# ESP32-Proto3-B.net
KiCad netlist of a schematic drawn in EAGLE
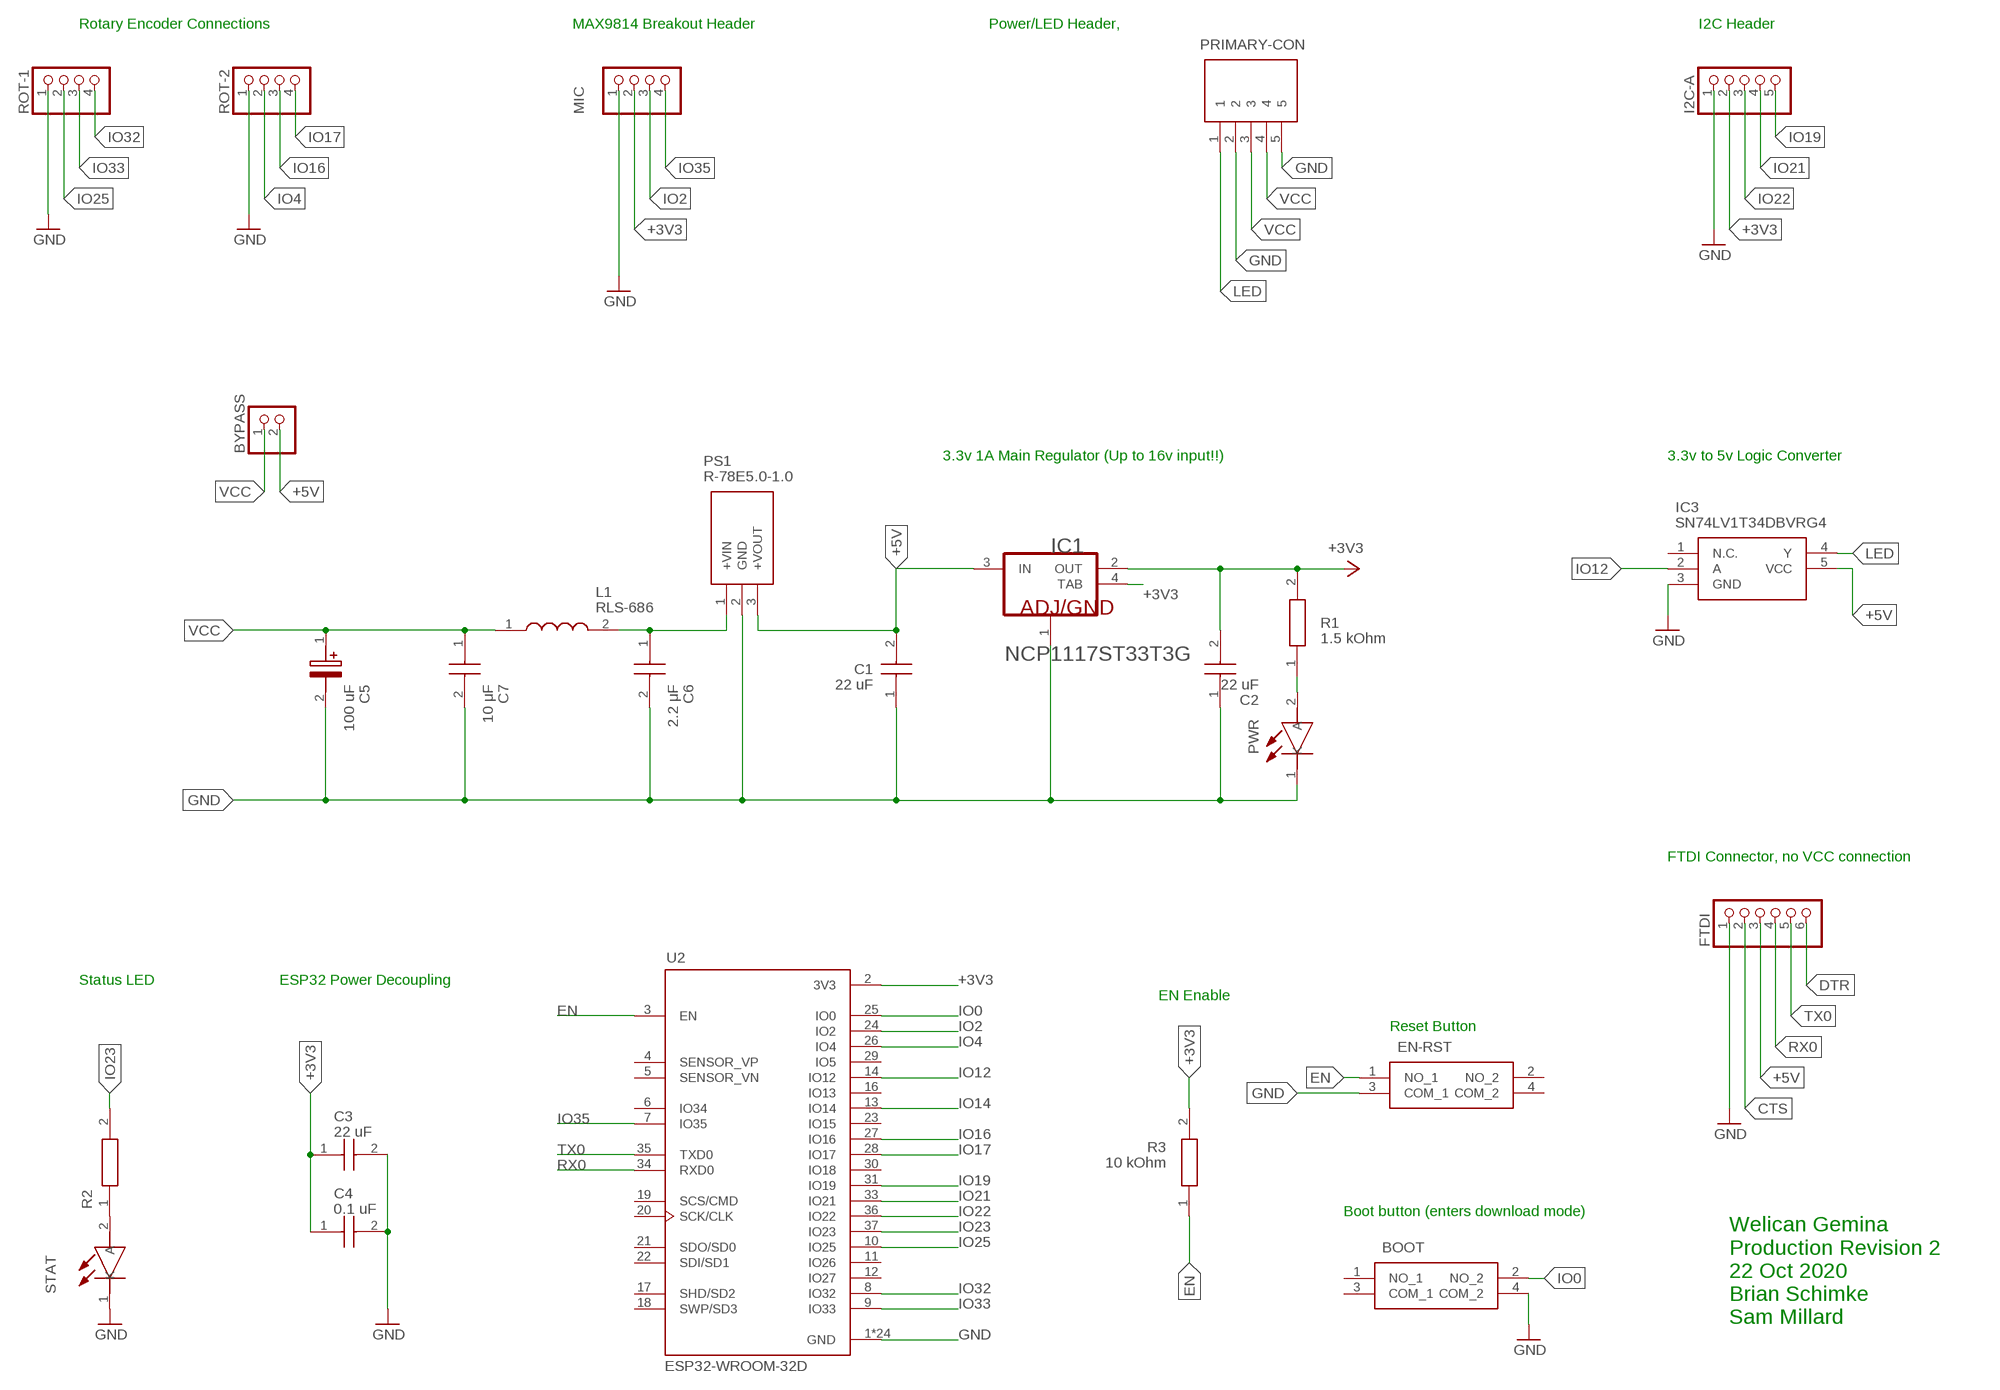
[diagram p0: schematic, sheet 1]

(export (version "E")
  (design (tool "Eeschema 10.0.6"))
  (components
    (comp (ref "BOOT")
      (value "PTS647SK70SMTR2LFS")
      (footprint "eagle-import:PTS647SK70SMTR2LFS")
      (fields (field (name "MOUSER_PART_NUMBER") "611-PTS647SK70SMTR2L"))
      (libsource (lib "eagle-import") (part "PTS647SK70SMTR2LFS"))
    )
    (comp (ref "BYPASS")
      (value "PINHD-1X2")
      (footprint "eagle-import:1X02")
      (libsource (lib "eagle-import") (part "PINHD-1X2"))
    )
    (comp (ref "C1")
      (value "22 uF")
      (footprint "eagle-import:CAPC3216X180N")
      (fields
        (field (name "MANUFACTURER_PART_NUMBER") "C1206C226M4PACTU")
        (field (name "MOUSER_PART_NUMBER") "80-C1206C226M4P")
      )
      (libsource (lib "eagle-import") (part "C1206C226M4PACTU"))
    )
    (comp (ref "C2")
      (value "22 uF")
      (footprint "eagle-import:CAPC3216X180N")
      (fields
        (field (name "MANUFACTURER_PART_NUMBER") "C1206C226M4PACTU")
        (field (name "MOUSER_PART_NUMBER") "80-C1206C226M4P")
      )
      (libsource (lib "eagle-import") (part "C1206C226M4PACTU"))
    )
    (comp (ref "C3")
      (value "22 uF")
      (footprint "eagle-import:CAPC3216X180N")
      (fields
        (field (name "MANUFACTURER_PART_NUMBER") "C1206C226M4PACTU")
        (field (name "MOUSER_PART_NUMBER") "80-C1206C226M4P")
      )
      (libsource (lib "eagle-import") (part "C1206C226M4PACTU"))
    )
    (comp (ref "C4")
      (value "0.1 uF")
      (footprint "eagle-import:CAPC3216X180N")
      (fields
        (field (name "MANUFACTURER_PART_NUMBER") "C1206C226M4PACTU")
        (field (name "MOUSER_PART_NUMBER") "80-C1206C226M4P")
      )
      (libsource (lib "eagle-import") (part "C1206C226M4PACTU"))
    )
    (comp (ref "C5")
      (value "100 uF")
      (footprint "eagle-import:CAPAE660X770N")
      (fields
        (field (name "MANUFACTURER_PART_NUMBER") "865080445010")
        (field (name "MOUSER_PART_NUMBER") "710-865080445010")
      )
      (libsource (lib "eagle-import") (part "865080445010"))
    )
    (comp (ref "C6")
      (value "2.2 μF")
      (footprint "eagle-import:CAPC3216X180N")
      (fields
        (field (name "MANUFACTURER_PART_NUMBER") "C1206C226M4PACTU")
        (field (name "MOUSER_PART_NUMBER") "80-C1206C226M4P")
      )
      (libsource (lib "eagle-import") (part "C1206C226M4PACTU"))
    )
    (comp (ref "C7")
      (value "10 μF")
      (footprint "eagle-import:CAPC3216X180N")
      (fields
        (field (name "MANUFACTURER_PART_NUMBER") "C1206C226M4PACTU")
        (field (name "MOUSER_PART_NUMBER") "80-C1206C226M4P")
      )
      (libsource (lib "eagle-import") (part "C1206C226M4PACTU"))
    )
    (comp (ref "EN-RST")
      (value "PTS647SK70SMTR2LFS")
      (footprint "eagle-import:PTS647SK70SMTR2LFS")
      (fields (field (name "MOUSER_PART_NUMBER") "611-PTS647SK70SMTR2L"))
      (libsource (lib "eagle-import") (part "PTS647SK70SMTR2LFS"))
    )
    (comp (ref "FTDI")
      (value "PINHD-1X6")
      (footprint "eagle-import:1X06")
      (libsource (lib "eagle-import") (part "PINHD-1X6"))
    )
    (comp (ref "I2C-A")
      (value "PINHD-1X5")
      (footprint "eagle-import:1X05")
      (libsource (lib "eagle-import") (part "PINHD-1X5"))
    )
    (comp (ref "IC1")
      (value "ON_SEMICONDUCTOR_NCP1117ST33T3GON_SEMICONDUCTOR_NCP1117ST33T3G_0_0")
      (footprint "eagle-import:ON_SEMICONDUCTOR_NCP1117ST33T3G_0")
      (fields
        (field (name "MF") "ON Semiconductor")
        (field (name "MPN") "NCP1117ST33T3G")
        (field (name "TOLERANCE") "1%")
      )
      (libsource (lib "eagle-import") (part "ON_SEMICONDUCTOR_NCP1117ST33T3GON_SEMICONDUCTOR_NCP1117ST33T3G_0_0"))
    )
    (comp (ref "IC3")
      (value "SN74LV1T34DBVRG4")
      (footprint "eagle-import:SOT95P280X145-5N")
      (fields (field (name "MOUSER_PART_NUMBER") "595-SN74LV1T34DBVRG4"))
      (libsource (lib "eagle-import") (part "SN74LV1T34DBVRG4"))
    )
    (comp (ref "L1")
      (value "RLS-686")
      (footprint "eagle-import:RLS686")
      (fields (field (name "MOUSER_PART_NUMBER") "919-RLS-686"))
      (libsource (lib "eagle-import") (part "RLS-686"))
    )
    (comp (ref "MIC")
      (value "PINHD-1X4")
      (footprint "eagle-import:1X04")
      (libsource (lib "eagle-import") (part "PINHD-1X4"))
    )
    (comp (ref "PRIMARY-CON")
      (value "1984646")
      (footprint "eagle-import:1984646")
      (libsource (lib "eagle-import") (part "1984646"))
    )
    (comp (ref "PS1")
      (value "R-78E5.0-1.0")
      (footprint "eagle-import:R78E5010")
      (fields (field (name "MOUSER_PART_NUMBER") "919-R-78E5.0-1.0"))
      (libsource (lib "eagle-import") (part "R-78E5.0-1.0"))
    )
    (comp (ref "PWR")
      (value "150120AS75000")
      (footprint "eagle-import:LEDSC320X160X78-2N")
      (fields (field (name "MOUSER_PART_NUMBER") "710-150120AS75000"))
      (libsource (lib "eagle-import") (part "150120AS75000"))
    )
    (comp (ref "R1")
      (value "1.5 kOhm")
      (footprint "eagle-import:RESC3216X60N")
      (fields
        (field (name "MANUFACTURER_PART_NUMBER") "CRCW12061K00FKEB")
        (field (name "MOUSER_PART_NUMBER") "71-CRCW12061K00FKEB")
      )
      (libsource (lib "eagle-import") (part "CRCW12061K00FKEB"))
    )
    (comp (ref "R2")
      (value "CRCW12061K00FKEB")
      (footprint "eagle-import:RESC3216X60N")
      (fields (field (name "MOUSER_PART_NUMBER") "71-CRCW12061K00FKEB"))
      (libsource (lib "eagle-import") (part "CRCW12061K00FKEB"))
    )
    (comp (ref "R3")
      (value "10 kOhm")
      (footprint "eagle-import:RESC3216X60N")
      (fields
        (field (name "MANUFACTURER_PART_NUMBER") "CRCW12061K00FKEB")
        (field (name "MOUSER_PART_NUMBER") "71-CRCW12061K00FKEB")
      )
      (libsource (lib "eagle-import") (part "CRCW12061K00FKEB"))
    )
    (comp (ref "ROT-1")
      (value "PINHD-1X4")
      (footprint "eagle-import:1X04")
      (libsource (lib "eagle-import") (part "PINHD-1X4"))
    )
    (comp (ref "ROT-2")
      (value "PINHD-1X4")
      (footprint "eagle-import:1X04")
      (libsource (lib "eagle-import") (part "PINHD-1X4"))
    )
    (comp (ref "STAT")
      (value "150120AS75000")
      (footprint "eagle-import:LEDSC320X160X78-2N")
      (fields (field (name "MOUSER_PART_NUMBER") "710-150120AS75000"))
      (libsource (lib "eagle-import") (part "150120AS75000"))
    )
    (comp (ref "U2")
      (value "ESP32-WROOM-32D")
      (footprint "eagle-import:MODULE_ESP32-WROOM-32D")
      (fields (field (name "MF") "Espressif Systems"))
      (libsource (lib "eagle-import") (part "ESP32-WROOM-32D"))
    )
  )
  (nets
    (net (code "1") (name "+3V3") (class "Default")
      (node (ref "C2") (pin "2") (pinfunction "2_2") (pintype "bidirectional"))
      (node (ref "C3") (pin "1") (pinfunction "1_1") (pintype "bidirectional"))
      (node (ref "C4") (pin "1") (pinfunction "1_1") (pintype "bidirectional"))
      (node (ref "I2C-A") (pin "2") (pinfunction "2_2") (pintype "passive"))
      (node (ref "IC1") (pin "2") (pinfunction "OUT_2") (pintype "power_in"))
      (node (ref "IC1") (pin "4") (pinfunction "TAB_4") (pintype "passive"))
      (node (ref "MIC") (pin "2") (pinfunction "2_2") (pintype "passive"))
      (node (ref "R1") (pin "2") (pinfunction "2_2") (pintype "bidirectional"))
      (node (ref "R3") (pin "2") (pinfunction "2_2") (pintype "bidirectional"))
      (node (ref "U2") (pin "2") (pinfunction "3V3_2") (pintype "power_in"))
    )
    (net (code "2") (name "+5V") (class "Default")
      (node (ref "BYPASS") (pin "2") (pinfunction "2_2") (pintype "passive"))
      (node (ref "C1") (pin "2") (pinfunction "2_2") (pintype "bidirectional"))
      (node (ref "FTDI") (pin "3") (pinfunction "3_3") (pintype "passive"))
      (node (ref "IC1") (pin "3") (pinfunction "IN_3") (pintype "power_in"))
      (node (ref "IC3") (pin "5") (pinfunction "VCC_5") (pintype "bidirectional"))
      (node (ref "PS1") (pin "3") (pinfunction "+VOUT_3") (pintype "bidirectional"))
    )
    (net (code "3") (name "/IO14") (class "Default")
      (node (ref "U2") (pin "13") (pinfunction "IO14_13") (pintype "bidirectional"))
    )
    (net (code "4") (name "CTS") (class "Default")
      (node (ref "FTDI") (pin "2") (pinfunction "2_2") (pintype "passive"))
    )
    (net (code "5") (name "DTR") (class "Default")
      (node (ref "FTDI") (pin "6") (pinfunction "6_6") (pintype "passive"))
    )
    (net (code "6") (name "EN") (class "Default")
      (node (ref "EN-RST") (pin "1") (pinfunction "NO_1_1") (pintype "bidirectional"))
      (node (ref "R3") (pin "1") (pinfunction "1_1") (pintype "bidirectional"))
      (node (ref "U2") (pin "3") (pinfunction "EN_3") (pintype "input"))
    )
    (net (code "7") (name "GND") (class "Default")
      (node (ref "BOOT") (pin "4") (pinfunction "COM_2_4") (pintype "bidirectional"))
      (node (ref "C1") (pin "1") (pinfunction "1_1") (pintype "bidirectional"))
      (node (ref "C2") (pin "1") (pinfunction "1_1") (pintype "bidirectional"))
      (node (ref "C3") (pin "2") (pinfunction "2_2") (pintype "bidirectional"))
      (node (ref "C4") (pin "2") (pinfunction "2_2") (pintype "bidirectional"))
      (node (ref "C5") (pin "2") (pinfunction "-_2") (pintype "bidirectional"))
      (node (ref "C6") (pin "2") (pinfunction "2_2") (pintype "bidirectional"))
      (node (ref "C7") (pin "2") (pinfunction "2_2") (pintype "bidirectional"))
      (node (ref "EN-RST") (pin "3") (pinfunction "COM_1_3") (pintype "bidirectional"))
      (node (ref "FTDI") (pin "1") (pinfunction "1_1") (pintype "passive"))
      (node (ref "I2C-A") (pin "1") (pinfunction "1_1") (pintype "passive"))
      (node (ref "IC1") (pin "1") (pinfunction "ADJ/GND_1") (pintype "passive"))
      (node (ref "IC3") (pin "3") (pinfunction "GND_3") (pintype "bidirectional"))
      (node (ref "MIC") (pin "1") (pinfunction "1_1") (pintype "passive"))
      (node (ref "PRIMARY-CON") (pin "2") (pinfunction "2_2") (pintype "bidirectional"))
      (node (ref "PRIMARY-CON") (pin "5") (pinfunction "5_5") (pintype "bidirectional"))
      (node (ref "PS1") (pin "2") (pinfunction "GND_2") (pintype "bidirectional"))
      (node (ref "PWR") (pin "1") (pinfunction "K_1") (pintype "bidirectional"))
      (node (ref "ROT-1") (pin "1") (pinfunction "1_1") (pintype "passive"))
      (node (ref "ROT-2") (pin "1") (pinfunction "1_1") (pintype "passive"))
      (node (ref "STAT") (pin "1") (pinfunction "K_1") (pintype "bidirectional"))
      (node (ref "U2") (pin "1") (pinfunction "GND_1") (pintype "power_in"))
      (node (ref "U2") (pin "15") (pinfunction "GND_15") (pintype "power_in"))
      (node (ref "U2") (pin "38") (pinfunction "GND_38") (pintype "power_in"))
      (node (ref "U2") (pin "39_1") (pinfunction "GND_39_1") (pintype "power_in"))
      (node (ref "U2") (pin "39_10") (pinfunction "GND_39_10") (pintype "power_in"))
      (node (ref "U2") (pin "39_11") (pinfunction "GND_39_11") (pintype "power_in"))
      (node (ref "U2") (pin "39_12") (pinfunction "GND_39_12") (pintype "power_in"))
      (node (ref "U2") (pin "39_13") (pinfunction "GND_39_13") (pintype "power_in"))
      (node (ref "U2") (pin "39_14") (pinfunction "GND_39_14") (pintype "power_in"))
      (node (ref "U2") (pin "39_15") (pinfunction "GND_39_15") (pintype "power_in"))
      (node (ref "U2") (pin "39_16") (pinfunction "GND_39_16") (pintype "power_in"))
      (node (ref "U2") (pin "39_17") (pinfunction "GND_39_17") (pintype "power_in"))
      (node (ref "U2") (pin "39_18") (pinfunction "GND_39_18") (pintype "power_in"))
      (node (ref "U2") (pin "39_19") (pinfunction "GND_39_19") (pintype "power_in"))
      (node (ref "U2") (pin "39_2") (pinfunction "GND_39_2") (pintype "power_in"))
      (node (ref "U2") (pin "39_20") (pinfunction "GND_39_20") (pintype "power_in"))
      (node (ref "U2") (pin "39_21") (pinfunction "GND_39_21") (pintype "power_in"))
      (node (ref "U2") (pin "39_3") (pinfunction "GND_39_3") (pintype "power_in"))
      (node (ref "U2") (pin "39_4") (pinfunction "GND_39_4") (pintype "power_in"))
      (node (ref "U2") (pin "39_5") (pinfunction "GND_39_5") (pintype "power_in"))
      (node (ref "U2") (pin "39_6") (pinfunction "GND_39_6") (pintype "power_in"))
      (node (ref "U2") (pin "39_7") (pinfunction "GND_39_7") (pintype "power_in"))
      (node (ref "U2") (pin "39_8") (pinfunction "GND_39_8") (pintype "power_in"))
      (node (ref "U2") (pin "39_9") (pinfunction "GND_39_9") (pintype "power_in"))
    )
    (net (code "8") (name "IO0") (class "Default")
      (node (ref "BOOT") (pin "2") (pinfunction "NO_2_2") (pintype "bidirectional"))
      (node (ref "U2") (pin "25") (pinfunction "IO0_25") (pintype "bidirectional"))
    )
    (net (code "9") (name "IO2") (class "Default")
      (node (ref "MIC") (pin "3") (pinfunction "3_3") (pintype "passive"))
      (node (ref "U2") (pin "24") (pinfunction "IO2_24") (pintype "bidirectional"))
    )
    (net (code "10") (name "IO4") (class "Default")
      (node (ref "ROT-2") (pin "2") (pinfunction "2_2") (pintype "passive"))
      (node (ref "U2") (pin "26") (pinfunction "IO4_26") (pintype "bidirectional"))
    )
    (net (code "11") (name "IO12") (class "Default")
      (node (ref "IC3") (pin "2") (pinfunction "A_2") (pintype "bidirectional"))
      (node (ref "U2") (pin "14") (pinfunction "IO12_14") (pintype "bidirectional"))
    )
    (net (code "12") (name "IO16") (class "Default")
      (node (ref "ROT-2") (pin "3") (pinfunction "3_3") (pintype "passive"))
      (node (ref "U2") (pin "27") (pinfunction "IO16_27") (pintype "bidirectional"))
    )
    (net (code "13") (name "IO17") (class "Default")
      (node (ref "ROT-2") (pin "4") (pinfunction "4_4") (pintype "passive"))
      (node (ref "U2") (pin "28") (pinfunction "IO17_28") (pintype "bidirectional"))
    )
    (net (code "14") (name "IO19") (class "Default")
      (node (ref "I2C-A") (pin "5") (pinfunction "5_5") (pintype "passive"))
      (node (ref "U2") (pin "31") (pinfunction "IO19_31") (pintype "bidirectional"))
    )
    (net (code "15") (name "IO21") (class "Default")
      (node (ref "I2C-A") (pin "4") (pinfunction "4_4") (pintype "passive"))
      (node (ref "U2") (pin "33") (pinfunction "IO21_33") (pintype "bidirectional"))
    )
    (net (code "16") (name "IO22") (class "Default")
      (node (ref "I2C-A") (pin "3") (pinfunction "3_3") (pintype "passive"))
      (node (ref "U2") (pin "36") (pinfunction "IO22_36") (pintype "bidirectional"))
    )
    (net (code "17") (name "IO23") (class "Default")
      (node (ref "R2") (pin "2") (pinfunction "2_2") (pintype "bidirectional"))
      (node (ref "U2") (pin "37") (pinfunction "IO23_37") (pintype "bidirectional"))
    )
    (net (code "18") (name "IO25") (class "Default")
      (node (ref "ROT-1") (pin "2") (pinfunction "2_2") (pintype "passive"))
      (node (ref "U2") (pin "10") (pinfunction "IO25_10") (pintype "bidirectional"))
    )
    (net (code "19") (name "IO32") (class "Default")
      (node (ref "ROT-1") (pin "4") (pinfunction "4_4") (pintype "passive"))
      (node (ref "U2") (pin "8") (pinfunction "IO32_8") (pintype "bidirectional"))
    )
    (net (code "20") (name "IO33") (class "Default")
      (node (ref "ROT-1") (pin "3") (pinfunction "3_3") (pintype "passive"))
      (node (ref "U2") (pin "9") (pinfunction "IO33_9") (pintype "bidirectional"))
    )
    (net (code "21") (name "IO35") (class "Default")
      (node (ref "MIC") (pin "4") (pinfunction "4_4") (pintype "passive"))
      (node (ref "U2") (pin "7") (pinfunction "IO35_7") (pintype "input"))
    )
    (net (code "22") (name "LED") (class "Default")
      (node (ref "IC3") (pin "4") (pinfunction "Y_4") (pintype "bidirectional"))
      (node (ref "PRIMARY-CON") (pin "1") (pinfunction "1_1") (pintype "bidirectional"))
    )
    (net (code "23") (name "Net-(PS1-+VIN)") (class "Default")
      (node (ref "C6") (pin "1") (pinfunction "1_1") (pintype "bidirectional"))
      (node (ref "L1") (pin "2") (pinfunction "2_2") (pintype "bidirectional"))
      (node (ref "PS1") (pin "1") (pinfunction "+VIN_1") (pintype "bidirectional"))
    )
    (net (code "24") (name "Net-(PWR-A)") (class "Default")
      (node (ref "PWR") (pin "2") (pinfunction "A_2") (pintype "bidirectional"))
      (node (ref "R1") (pin "1") (pinfunction "1_1") (pintype "bidirectional"))
    )
    (net (code "25") (name "Net-(STAT-A)") (class "Default")
      (node (ref "R2") (pin "1") (pinfunction "1_1") (pintype "bidirectional"))
      (node (ref "STAT") (pin "2") (pinfunction "A_2") (pintype "bidirectional"))
    )
    (net (code "26") (name "RX0") (class "Default")
      (node (ref "FTDI") (pin "4") (pinfunction "4_4") (pintype "passive"))
      (node (ref "U2") (pin "34") (pinfunction "RXD0_34") (pintype "bidirectional"))
    )
    (net (code "27") (name "TX0") (class "Default")
      (node (ref "FTDI") (pin "5") (pinfunction "5_5") (pintype "passive"))
      (node (ref "U2") (pin "35") (pinfunction "TXD0_35") (pintype "bidirectional"))
    )
    (net (code "28") (name "VCC") (class "Default")
      (node (ref "BYPASS") (pin "1") (pinfunction "1_1") (pintype "passive"))
      (node (ref "C5") (pin "1") (pinfunction "+_1") (pintype "bidirectional"))
      (node (ref "C7") (pin "1") (pinfunction "1_1") (pintype "bidirectional"))
      (node (ref "L1") (pin "1") (pinfunction "1_1") (pintype "bidirectional"))
      (node (ref "PRIMARY-CON") (pin "3") (pinfunction "3_3") (pintype "bidirectional"))
      (node (ref "PRIMARY-CON") (pin "4") (pinfunction "4_4") (pintype "bidirectional"))
    )
    (net (code "29") (name "unconnected-(BOOT-COM_1-Pad3)") (class "Default")
      (node (ref "BOOT") (pin "3") (pinfunction "COM_1_3") (pintype "bidirectional"))
    )
    (net (code "30") (name "unconnected-(BOOT-NO_1-Pad1)") (class "Default")
      (node (ref "BOOT") (pin "1") (pinfunction "NO_1_1") (pintype "bidirectional"))
    )
    (net (code "31") (name "unconnected-(EN-RST-COM_2-Pad4)") (class "Default")
      (node (ref "EN-RST") (pin "4") (pinfunction "COM_2_4") (pintype "bidirectional"))
    )
    (net (code "32") (name "unconnected-(EN-RST-NO_2-Pad2)") (class "Default")
      (node (ref "EN-RST") (pin "2") (pinfunction "NO_2_2") (pintype "bidirectional"))
    )
    (net (code "33") (name "unconnected-(IC3-N.C.-Pad1)") (class "Default")
      (node (ref "IC3") (pin "1") (pinfunction "N.C._1") (pintype "no_connect"))
    )
    (net (code "34") (name "unconnected-(U2-IO5-Pad29)") (class "Default")
      (node (ref "U2") (pin "29") (pinfunction "IO5_29") (pintype "bidirectional"))
    )
    (net (code "35") (name "unconnected-(U2-IO13-Pad16)") (class "Default")
      (node (ref "U2") (pin "16") (pinfunction "IO13_16") (pintype "bidirectional"))
    )
    (net (code "36") (name "unconnected-(U2-IO15-Pad23)") (class "Default")
      (node (ref "U2") (pin "23") (pinfunction "IO15_23") (pintype "bidirectional"))
    )
    (net (code "37") (name "unconnected-(U2-IO18-Pad30)") (class "Default")
      (node (ref "U2") (pin "30") (pinfunction "IO18_30") (pintype "bidirectional"))
    )
    (net (code "38") (name "unconnected-(U2-IO26-Pad11)") (class "Default")
      (node (ref "U2") (pin "11") (pinfunction "IO26_11") (pintype "bidirectional"))
    )
    (net (code "39") (name "unconnected-(U2-IO27-Pad12)") (class "Default")
      (node (ref "U2") (pin "12") (pinfunction "IO27_12") (pintype "bidirectional"))
    )
    (net (code "40") (name "unconnected-(U2-IO34-Pad6)") (class "Default")
      (node (ref "U2") (pin "6") (pinfunction "IO34_6") (pintype "input"))
    )
    (net (code "41") (name "unconnected-(U2-SCK{slash}CLK-Pad20)") (class "Default")
      (node (ref "U2") (pin "20") (pinfunction "SCK/CLK_20") (pintype "bidirectional"))
    )
    (net (code "42") (name "unconnected-(U2-SCS{slash}CMD-Pad19)") (class "Default")
      (node (ref "U2") (pin "19") (pinfunction "SCS/CMD_19") (pintype "bidirectional"))
    )
    (net (code "43") (name "unconnected-(U2-SDI{slash}SD1-Pad22)") (class "Default")
      (node (ref "U2") (pin "22") (pinfunction "SDI/SD1_22") (pintype "bidirectional"))
    )
    (net (code "44") (name "unconnected-(U2-SDO{slash}SD0-Pad21)") (class "Default")
      (node (ref "U2") (pin "21") (pinfunction "SDO/SD0_21") (pintype "bidirectional"))
    )
    (net (code "45") (name "unconnected-(U2-SENSOR_VN-Pad5)") (class "Default")
      (node (ref "U2") (pin "5") (pinfunction "SENSOR_VN_5") (pintype "input"))
    )
    (net (code "46") (name "unconnected-(U2-SENSOR_VP-Pad4)") (class "Default")
      (node (ref "U2") (pin "4") (pinfunction "SENSOR_VP_4") (pintype "input"))
    )
    (net (code "47") (name "unconnected-(U2-SHD{slash}SD2-Pad17)") (class "Default")
      (node (ref "U2") (pin "17") (pinfunction "SHD/SD2_17") (pintype "bidirectional"))
    )
    (net (code "48") (name "unconnected-(U2-SWP{slash}SD3-Pad18)") (class "Default")
      (node (ref "U2") (pin "18") (pinfunction "SWP/SD3_18") (pintype "bidirectional"))
    )
  )
)
